# USB-IRIS-W1_MODULE.net
KiCad netlist of a schematic drawn in Altium Designer
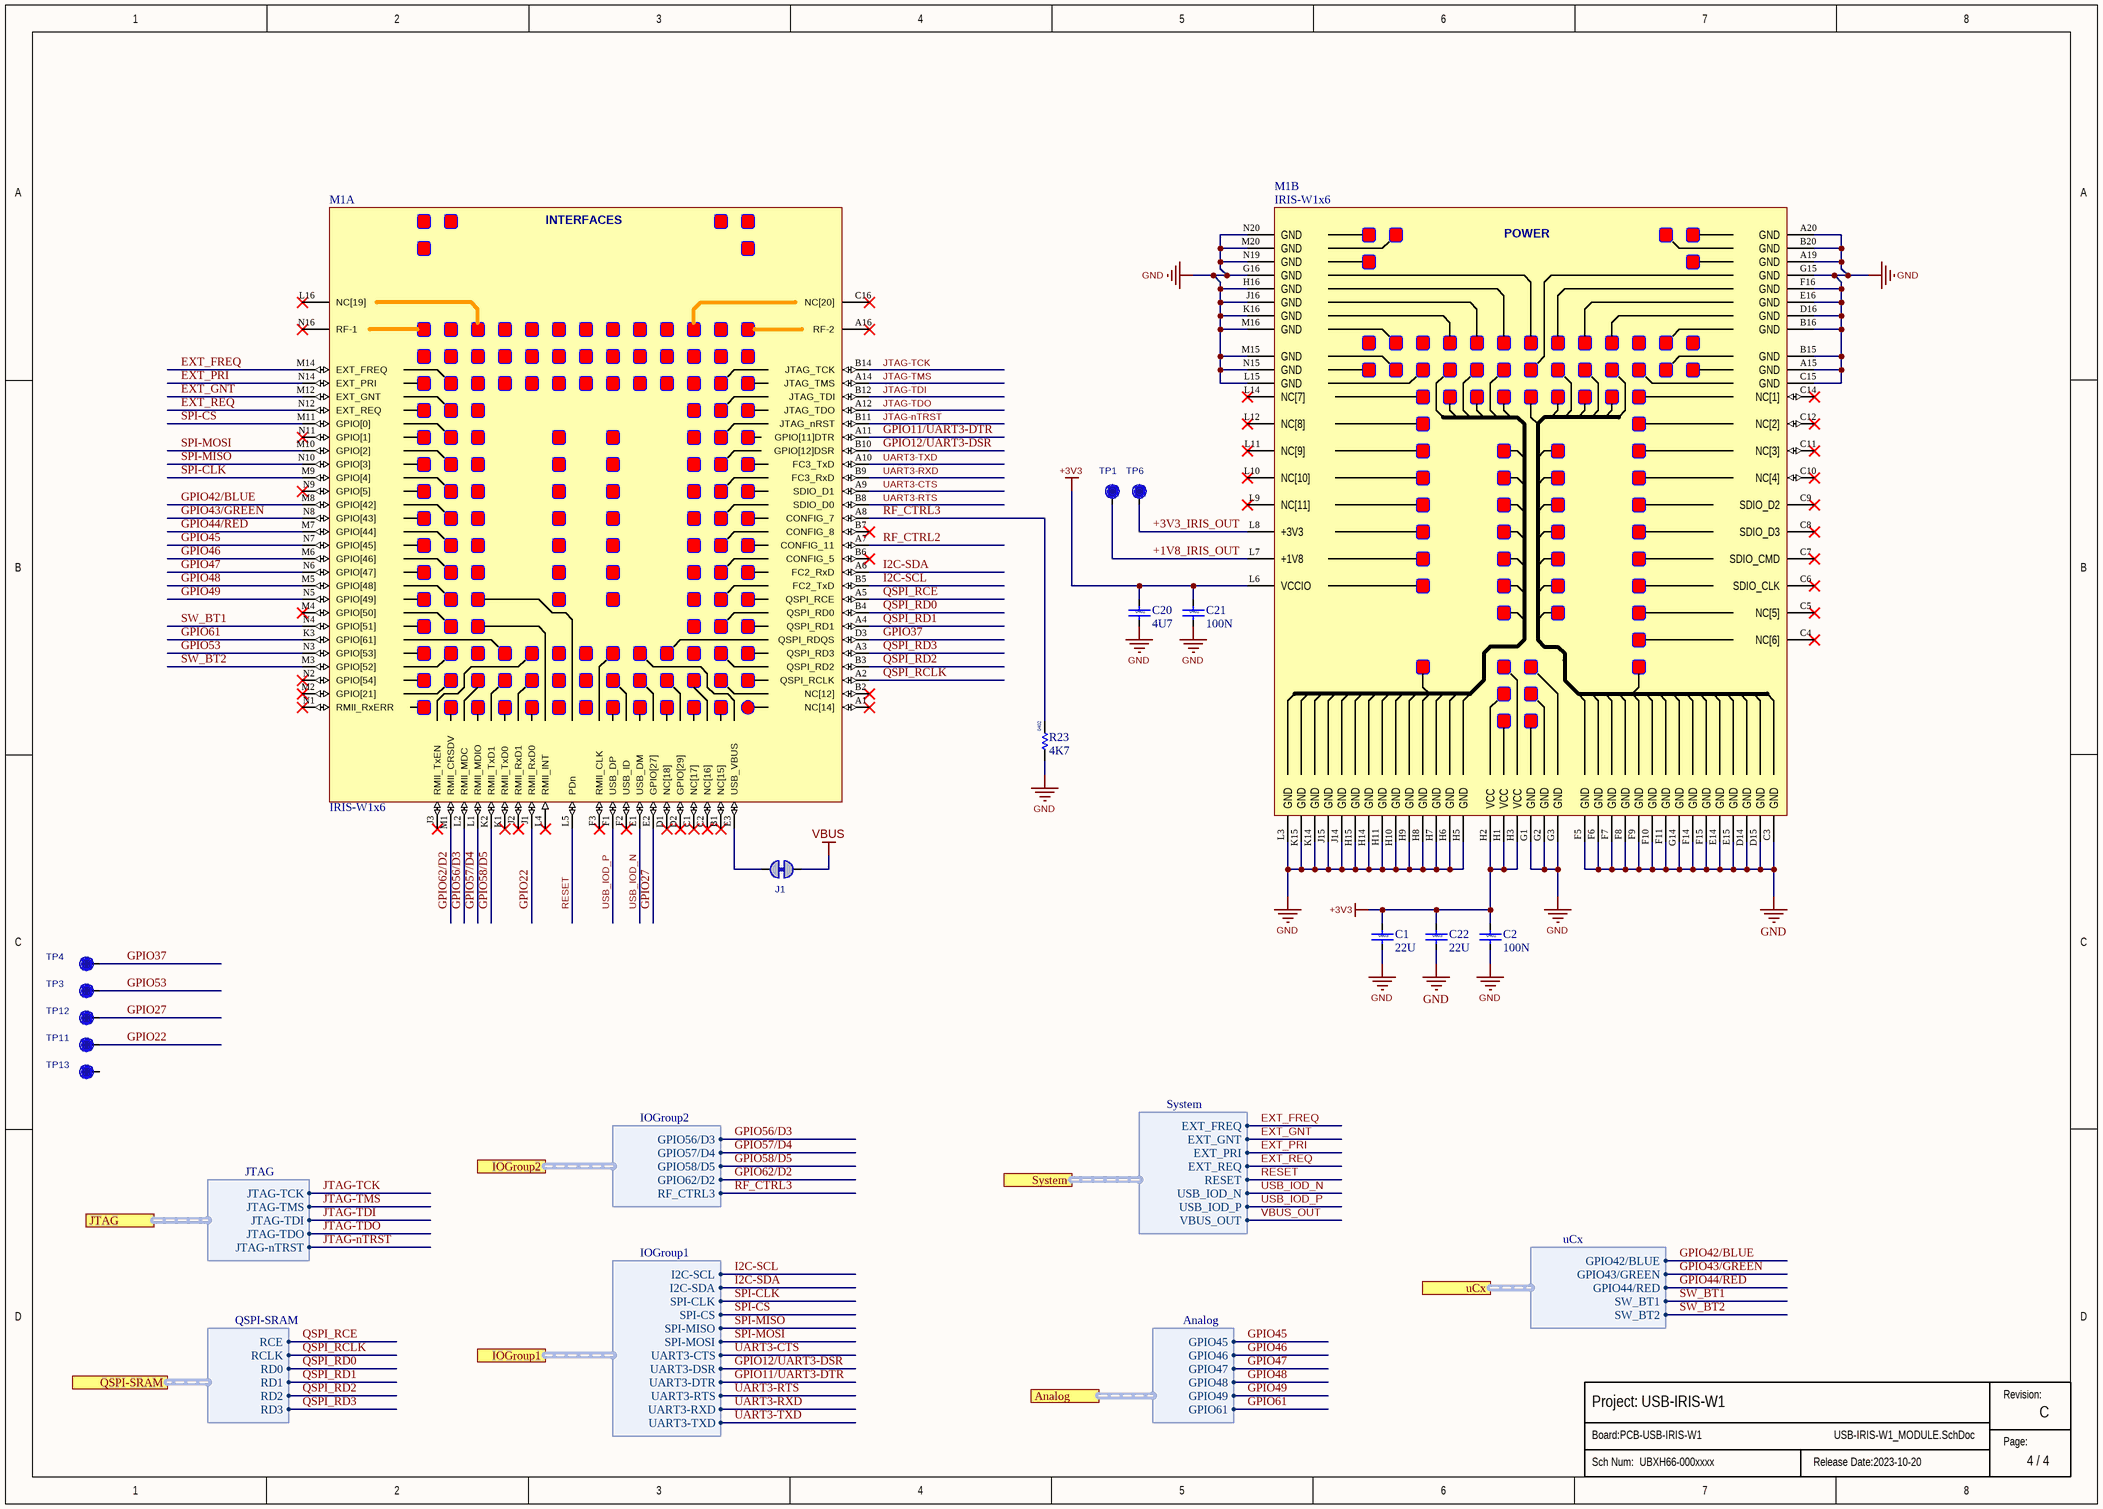
[diagram p0: USB-IRIS-W1_MODULE.SchDoc]

(export (version "E")
  (design (tool "Eeschema 10.0.6"))
  (components
    (comp (ref "C1")
      (value "22U")
      (footprint "Cap 0603")
      (description "CAP CER X5R 0603 22U 20% 10V")
      (fields
        (field (name "SIZE") "0603")
        (field (name "PART NUMBER") "UBXH01-0000150")
        (field (name "TOLERANCE") "20%")
        (field (name "EDITOR") "dario.antonaz")
        (field (name "RELEASED BY") "pasquale.scorca")
      )
      (libsource (lib "UBX_Parts_DB_Lib") (part "Cap Chip"))
    )
    (comp (ref "C2")
      (value "100N")
      (footprint "Cap 0402 HD")
      (description "CAP CER X5R 0402 100N 10% 10V")
      (fields
        (field (name "SIZE") "0402")
        (field (name "PART NUMBER") "UBXH01-2021002")
        (field (name "TOLERANCE") "10%")
        (field (name "EDITOR") "roland.rust")
        (field (name "RELEASED BY") "roland.rust")
      )
      (libsource (lib "UBX_Parts_DB_Lib") (part "Cap Chip"))
    )
    (comp (ref "C20")
      (value "4U7")
      (footprint "Cap_0402_1200Lx700Wx700H_600x600Pad_350G_FLX")
      (description "CAP CER X5R 0402 4U7 20% 10V")
      (fields
        (field (name "SIZE") "0402")
        (field (name "PART NUMBER") "UBXH01-0000243")
        (field (name "TOLERANCE") "20%")
        (field (name "EDITOR") "martin.pilik")
        (field (name "RELEASED BY") "fabrice.bret-dibat")
      )
      (libsource (lib "UBX_Parts_DB_Lib") (part "Cap Chip"))
    )
    (comp (ref "C21")
      (value "100N")
      (footprint "Cap 0402 HD")
      (description "CAP CER X5R 0402 100N 10% 10V")
      (fields
        (field (name "SIZE") "0402")
        (field (name "PART NUMBER") "UBXH01-2021002")
        (field (name "TOLERANCE") "10%")
        (field (name "EDITOR") "roland.rust")
        (field (name "RELEASED BY") "roland.rust")
      )
      (libsource (lib "UBX_Parts_DB_Lib") (part "Cap Chip"))
    )
    (comp (ref "C22")
      (value "22U")
      (footprint "Cap 0603")
      (description "CAP CER X5R 0603 22U 20% 10V")
      (fields
        (field (name "SIZE") "0603")
        (field (name "PART NUMBER") "UBXH01-0000150")
        (field (name "TOLERANCE") "20%")
        (field (name "EDITOR") "dario.antonaz")
        (field (name "RELEASED BY") "pasquale.scorca")
      )
      (libsource (lib "UBX_Parts_DB_Lib") (part "Cap Chip"))
    )
    (comp (ref "J1")
      (value "Solderbridge-ShortDNP")
      (footprint "Solderbridge-Short")
      (description "Solderbridge-Short")
      (fields (field (name "ADDED BY") "Paul B"))
      (libsource (lib "Schlib1") (part "Solderbridge-Short"))
    )
    (comp (ref "M1")
      (value "IRIS-W1x6")
      (footprint "IRIS-W1x6_LGA152")
      (description "SHORT RANGE STAND-ALONE MULTIRADIO MODULE U-BLOX IRIS-W106")
      (fields (field (name "PART NUMBER") "UBXH14-0000681") (field (name "EDITOR") "olof.viklund"))
      (libsource (lib "UBX_Parts_DB_Lib") (part "IRIS-W1_152pin"))
    )
    (comp (ref "R23")
      (value "4K7")
      (footprint "RES_0402_1100Lx600Wx400H_500x600Pad_400G_FLX")
      (description "RES THICK FILM CHIP 0402 4K7 5% 100mW")
      (fields
        (field (name "SIZE") "0402")
        (field (name "PART NUMBER") "UBXH18-0008065")
        (field (name "TOLERANCE") "5%")
        (field (name "EDITOR") "martin.frauchiger")
        (field (name "RELEASED BY") "martin.frauchiger")
      )
      (libsource (lib "UBX_Parts_DB_Lib") (part "Res sm"))
    )
    (comp (ref "TP1")
      (value "TP")
      (footprint "TP10R")
      (description "Testpoint, Round 1.0mm Dia")
      (fields
        (field (name "PART NUMBER") "TP10R")
        (field (name "ADDED BY") "Jeremy D")
        (field (name "CHECKED BY") "Paul B")
      )
      (libsource (lib "") (part "TP_R_1"))
    )
    (comp (ref "TP3")
      (value "TP")
      (footprint "TP10R")
      (description "Testpoint, Round 1.0mm Dia")
      (fields
        (field (name "PART NUMBER") "TP10R")
        (field (name "ADDED BY") "Jeremy D")
        (field (name "CHECKED BY") "Paul B")
      )
      (libsource (lib "LEGACY_Rigado_AltiumLib") (part "TP_R"))
    )
    (comp (ref "TP4")
      (value "TP")
      (footprint "TP10R")
      (description "Testpoint, Round 1.0mm Dia")
      (fields
        (field (name "PART NUMBER") "TP10R")
        (field (name "ADDED BY") "Jeremy D")
        (field (name "CHECKED BY") "Paul B")
      )
      (libsource (lib "LEGACY_Rigado_AltiumLib") (part "TP_R"))
    )
    (comp (ref "TP6")
      (value "TP")
      (footprint "TP10R")
      (description "Testpoint, Round 1.0mm Dia")
      (fields
        (field (name "PART NUMBER") "TP10R")
        (field (name "ADDED BY") "Jeremy D")
        (field (name "CHECKED BY") "Paul B")
      )
      (libsource (lib "") (part "TP_R_1"))
    )
    (comp (ref "TP11")
      (value "TP")
      (footprint "TP10R")
      (description "Testpoint, Round 1.0mm Dia")
      (fields
        (field (name "PART NUMBER") "TP10R")
        (field (name "ADDED BY") "Jeremy D")
        (field (name "CHECKED BY") "Paul B")
      )
      (libsource (lib "LEGACY_Rigado_AltiumLib") (part "TP_R"))
    )
    (comp (ref "TP12")
      (value "TP")
      (footprint "TP10R")
      (description "Testpoint, Round 1.0mm Dia")
      (fields
        (field (name "PART NUMBER") "TP10R")
        (field (name "ADDED BY") "Jeremy D")
        (field (name "CHECKED BY") "Paul B")
      )
      (libsource (lib "LEGACY_Rigado_AltiumLib") (part "TP_R"))
    )
    (comp (ref "TP13")
      (value "TP")
      (footprint "TP10R")
      (description "Testpoint, Round 1.0mm Dia")
      (fields
        (field (name "PART NUMBER") "TP10R")
        (field (name "ADDED BY") "Jeremy D")
        (field (name "CHECKED BY") "Paul B")
      )
      (libsource (lib "LEGACY_Rigado_AltiumLib") (part "TP_R"))
    )
  )
  (nets
    (net (code "8") (name "+3V3") (class "Default")
      (node (ref "C1") (pin "1") (pinfunction "1_1") (pintype "passive"))
      (node (ref "C2") (pin "1") (pinfunction "1_1") (pintype "passive"))
      (node (ref "C20") (pin "1") (pinfunction "1_1") (pintype "passive"))
      (node (ref "C21") (pin "1") (pinfunction "1_1") (pintype "passive"))
      (node (ref "C22") (pin "1") (pinfunction "1_1") (pintype "passive"))
      (node (ref "M1") (pin "H1") (pinfunction "VCC_H1") (pintype "power_in"))
      (node (ref "M1") (pin "H2") (pinfunction "VCC_H2") (pintype "power_in"))
      (node (ref "M1") (pin "H3") (pinfunction "VCC_H3") (pintype "power_in"))
      (node (ref "M1") (pin "L6") (pinfunction "VCCIO_L6") (pintype "power_in"))
    )
    (net (code "9") (name "/+1V8_IRIS_OUT") (class "Default")
      (node (ref "M1") (pin "L7") (pinfunction "+1V8_L7") (pintype "power_in"))
      (node (ref "TP1") (pin "1") (pintype "passive"))
    )
    (net (code "10") (name "/+3V3_IRIS_OUT") (class "Default")
      (node (ref "M1") (pin "L8") (pinfunction "+3V3_L8") (pintype "power_in"))
      (node (ref "TP6") (pin "1") (pintype "passive"))
    )
    (net (code "11") (name "/EXT_FREQ") (class "Default")
      (node (ref "M1") (pin "M14") (pinfunction "EXT_FREQ_M14") (pintype "bidirectional"))
    )
    (net (code "12") (name "/EXT_GNT") (class "Default")
      (node (ref "M1") (pin "M12") (pinfunction "EXT_GNT_M12") (pintype "bidirectional"))
    )
    (net (code "13") (name "/EXT_PRI") (class "Default")
      (node (ref "M1") (pin "N14") (pinfunction "EXT_PRI_N14") (pintype "bidirectional"))
    )
    (net (code "14") (name "/EXT_REQ") (class "Default")
      (node (ref "M1") (pin "N12") (pinfunction "EXT_REQ_N12") (pintype "bidirectional"))
    )
    (net (code "15") (name "/GPIO11{slash}UART3-DTR") (class "Default")
      (node (ref "M1") (pin "A11") (pinfunction "GPIO[11]DTR_A11") (pintype "bidirectional"))
    )
    (net (code "16") (name "/GPIO12{slash}UART3-DSR") (class "Default")
      (node (ref "M1") (pin "B10") (pinfunction "GPIO[12]DSR_B10") (pintype "bidirectional"))
    )
    (net (code "17") (name "/GPIO22") (class "Default")
      (node (ref "M1") (pin "J1") (pinfunction "RMII_RxD0_J1") (pintype "bidirectional"))
      (node (ref "TP11") (pin "1") (pintype "passive"))
    )
    (net (code "18") (name "/GPIO27") (class "Default")
      (node (ref "M1") (pin "E2") (pinfunction "GPIO[27]_E2") (pintype "bidirectional"))
      (node (ref "TP12") (pin "1") (pintype "passive"))
    )
    (net (code "19") (name "/GPIO37") (class "Default")
      (node (ref "M1") (pin "D3") (pinfunction "QSPI_RDQS_D3") (pintype "bidirectional"))
      (node (ref "TP4") (pin "1") (pintype "passive"))
    )
    (net (code "20") (name "/GPIO42{slash}BLUE") (class "Default")
      (node (ref "M1") (pin "M8") (pinfunction "GPIO[42]_M8") (pintype "bidirectional"))
    )
    (net (code "21") (name "/GPIO43{slash}GREEN") (class "Default")
      (node (ref "M1") (pin "N8") (pinfunction "GPIO[43]_N8") (pintype "bidirectional"))
    )
    (net (code "22") (name "/GPIO44{slash}RED") (class "Default")
      (node (ref "M1") (pin "M7") (pinfunction "GPIO[44]_M7") (pintype "bidirectional"))
    )
    (net (code "23") (name "/GPIO45") (class "Default")
      (node (ref "M1") (pin "N7") (pinfunction "GPIO[45]_N7") (pintype "bidirectional"))
    )
    (net (code "24") (name "/GPIO46") (class "Default")
      (node (ref "M1") (pin "M6") (pinfunction "GPIO[46]_M6") (pintype "bidirectional"))
    )
    (net (code "25") (name "/GPIO47") (class "Default")
      (node (ref "M1") (pin "N6") (pinfunction "GPIO[47]_N6") (pintype "bidirectional"))
    )
    (net (code "26") (name "/GPIO48") (class "Default")
      (node (ref "M1") (pin "M5") (pinfunction "GPIO[48]_M5") (pintype "bidirectional"))
    )
    (net (code "27") (name "/GPIO49") (class "Default")
      (node (ref "M1") (pin "N5") (pinfunction "GPIO[49]_N5") (pintype "bidirectional"))
    )
    (net (code "28") (name "/GPIO53") (class "Default")
      (node (ref "M1") (pin "N3") (pinfunction "GPIO[53]_N3") (pintype "bidirectional"))
      (node (ref "TP3") (pin "1") (pintype "passive"))
    )
    (net (code "29") (name "/GPIO56{slash}D3") (class "Default")
      (node (ref "M1") (pin "L2") (pinfunction "RMII_MDC_L2") (pintype "bidirectional"))
    )
    (net (code "30") (name "/GPIO57{slash}D4") (class "Default")
      (node (ref "M1") (pin "L1") (pinfunction "RMII_MDIO_L1") (pintype "bidirectional"))
    )
    (net (code "31") (name "/GPIO58{slash}D5") (class "Default")
      (node (ref "M1") (pin "K2") (pinfunction "RMII_TxD1_K2") (pintype "bidirectional"))
    )
    (net (code "32") (name "/GPIO61") (class "Default")
      (node (ref "M1") (pin "K3") (pinfunction "GPIO[61]_K3") (pintype "bidirectional"))
    )
    (net (code "33") (name "/GPIO62{slash}D2") (class "Default")
      (node (ref "M1") (pin "M1") (pinfunction "RMII_CRSDV_M1") (pintype "bidirectional"))
    )
    (net (code "34") (name "/I2C-SCL") (class "Default")
      (node (ref "M1") (pin "B5") (pinfunction "FC2_TxD_B5") (pintype "bidirectional"))
    )
    (net (code "35") (name "/I2C-SDA") (class "Default")
      (node (ref "M1") (pin "A6") (pinfunction "FC2_RxD_A6") (pintype "bidirectional"))
    )
    (net (code "36") (name "/JTAG-TCK") (class "Default")
      (node (ref "M1") (pin "B14") (pinfunction "JTAG_TCK_B14") (pintype "bidirectional"))
    )
    (net (code "37") (name "/JTAG-TDI") (class "Default")
      (node (ref "M1") (pin "B12") (pinfunction "JTAG_TDI_B12") (pintype "bidirectional"))
    )
    (net (code "38") (name "/JTAG-TDO") (class "Default")
      (node (ref "M1") (pin "A12") (pinfunction "JTAG_TDO_A12") (pintype "bidirectional"))
    )
    (net (code "39") (name "/JTAG-TMS") (class "Default")
      (node (ref "M1") (pin "A14") (pinfunction "JTAG_TMS_A14") (pintype "bidirectional"))
    )
    (net (code "40") (name "/JTAG-nTRST") (class "Default")
      (node (ref "M1") (pin "B11") (pinfunction "JTAG_nRST_B11") (pintype "bidirectional"))
    )
    (net (code "41") (name "/QSPI_RCE") (class "Default")
      (node (ref "M1") (pin "A5") (pinfunction "QSPI_RCE_A5") (pintype "bidirectional"))
    )
    (net (code "42") (name "/QSPI_RCLK") (class "Default")
      (node (ref "M1") (pin "A2") (pinfunction "QSPI_RCLK_A2") (pintype "bidirectional"))
    )
    (net (code "43") (name "/QSPI_RD0") (class "Default")
      (node (ref "M1") (pin "B4") (pinfunction "QSPI_RD0_B4") (pintype "bidirectional"))
    )
    (net (code "44") (name "/QSPI_RD1") (class "Default")
      (node (ref "M1") (pin "A4") (pinfunction "QSPI_RD1_A4") (pintype "bidirectional"))
    )
    (net (code "45") (name "/QSPI_RD2") (class "Default")
      (node (ref "M1") (pin "B3") (pinfunction "QSPI_RD2_B3") (pintype "bidirectional"))
    )
    (net (code "46") (name "/QSPI_RD3") (class "Default")
      (node (ref "M1") (pin "A3") (pinfunction "QSPI_RD3_A3") (pintype "bidirectional"))
    )
    (net (code "47") (name "/RESET") (class "Default")
      (node (ref "M1") (pin "L5") (pinfunction "PDn_L5") (pintype "bidirectional"))
    )
    (net (code "48") (name "/RF_CTRL2") (class "Default")
      (node (ref "M1") (pin "A7") (pinfunction "CONFIG_11_A7") (pintype "bidirectional"))
    )
    (net (code "49") (name "/RF_CTRL3") (class "Default")
      (node (ref "M1") (pin "A8") (pinfunction "CONFIG_7_A8") (pintype "bidirectional"))
      (node (ref "R23") (pin "2") (pinfunction "2_2") (pintype "passive"))
    )
    (net (code "50") (name "/SPI-CLK") (class "Default")
      (node (ref "M1") (pin "M9") (pinfunction "GPIO[4]_M9") (pintype "bidirectional"))
    )
    (net (code "51") (name "/SPI-CS") (class "Default")
      (node (ref "M1") (pin "M11") (pinfunction "GPIO[0]_M11") (pintype "bidirectional"))
    )
    (net (code "52") (name "/SPI-MISO") (class "Default")
      (node (ref "M1") (pin "N10") (pinfunction "GPIO[3]_N10") (pintype "bidirectional"))
    )
    (net (code "53") (name "/SPI-MOSI") (class "Default")
      (node (ref "M1") (pin "M10") (pinfunction "GPIO[2]_M10") (pintype "bidirectional"))
    )
    (net (code "54") (name "/SW_BT1") (class "Default")
      (node (ref "M1") (pin "N4") (pinfunction "GPIO[51]_N4") (pintype "bidirectional"))
    )
    (net (code "55") (name "/SW_BT2") (class "Default")
      (node (ref "M1") (pin "M3") (pinfunction "GPIO[52]_M3") (pintype "bidirectional"))
    )
    (net (code "56") (name "/UART3-CTS") (class "Default")
      (node (ref "M1") (pin "A9") (pinfunction "SDIO_D1_A9") (pintype "bidirectional"))
    )
    (net (code "57") (name "/UART3-RTS") (class "Default")
      (node (ref "M1") (pin "B8") (pinfunction "SDIO_D0_B8") (pintype "bidirectional"))
    )
    (net (code "58") (name "/UART3-RXD") (class "Default")
      (node (ref "M1") (pin "B9") (pinfunction "FC3_RxD_B9") (pintype "bidirectional"))
    )
    (net (code "59") (name "/UART3-TXD") (class "Default")
      (node (ref "M1") (pin "A10") (pinfunction "FC3_TxD_A10") (pintype "bidirectional"))
    )
    (net (code "60") (name "/USB_IOD_N") (class "Default")
      (node (ref "M1") (pin "E1") (pinfunction "USB_DM_E1") (pintype "bidirectional"))
    )
    (net (code "61") (name "/USB_IOD_P") (class "Default")
      (node (ref "M1") (pin "F1") (pinfunction "USB_DP_F1") (pintype "bidirectional"))
    )
    (net (code "70") (name "GND") (class "Default")
      (node (ref "C1") (pin "2") (pinfunction "2_2") (pintype "passive"))
      (node (ref "C2") (pin "2") (pinfunction "2_2") (pintype "passive"))
      (node (ref "C20") (pin "2") (pinfunction "2_2") (pintype "passive"))
      (node (ref "C21") (pin "2") (pinfunction "2_2") (pintype "passive"))
      (node (ref "C22") (pin "2") (pinfunction "2_2") (pintype "passive"))
      (node (ref "M1") (pin "A15") (pinfunction "GND_A15") (pintype "power_in"))
      (node (ref "M1") (pin "A19") (pinfunction "GND_A19") (pintype "passive"))
      (node (ref "M1") (pin "A20") (pinfunction "GND_A20") (pintype "passive"))
      (node (ref "M1") (pin "B15") (pinfunction "GND_B15") (pintype "power_in"))
      (node (ref "M1") (pin "B16") (pinfunction "GND_B16") (pintype "power_in"))
      (node (ref "M1") (pin "B20") (pinfunction "GND_B20") (pintype "passive"))
      (node (ref "M1") (pin "C15") (pinfunction "GND_C15") (pintype "power_in"))
      (node (ref "M1") (pin "C3") (pinfunction "GND_C3") (pintype "power_in"))
      (node (ref "M1") (pin "D14") (pinfunction "GND_D14") (pintype "power_in"))
      (node (ref "M1") (pin "D15") (pinfunction "GND_D15") (pintype "power_in"))
      (node (ref "M1") (pin "D16") (pinfunction "GND_D16") (pintype "power_in"))
      (node (ref "M1") (pin "E14") (pinfunction "GND_E14") (pintype "power_in"))
      (node (ref "M1") (pin "E15") (pinfunction "GND_E15") (pintype "power_in"))
      (node (ref "M1") (pin "E16") (pinfunction "GND_E16") (pintype "power_in"))
      (node (ref "M1") (pin "F10") (pinfunction "GND_F10") (pintype "power_in"))
      (node (ref "M1") (pin "F11") (pinfunction "GND_F11") (pintype "power_in"))
      (node (ref "M1") (pin "F14") (pinfunction "GND_F14") (pintype "power_in"))
      (node (ref "M1") (pin "F15") (pinfunction "GND_F15") (pintype "power_in"))
      (node (ref "M1") (pin "F16") (pinfunction "GND_F16") (pintype "power_in"))
      (node (ref "M1") (pin "F5") (pinfunction "GND_F5") (pintype "power_in"))
      (node (ref "M1") (pin "F6") (pinfunction "GND_F6") (pintype "power_in"))
      (node (ref "M1") (pin "F7") (pinfunction "GND_F7") (pintype "power_in"))
      (node (ref "M1") (pin "F8") (pinfunction "GND_F8") (pintype "power_in"))
      (node (ref "M1") (pin "F9") (pinfunction "GND_F9") (pintype "power_in"))
      (node (ref "M1") (pin "G1") (pinfunction "GND_G1") (pintype "power_in"))
      (node (ref "M1") (pin "G14") (pinfunction "GND_G14") (pintype "power_in"))
      (node (ref "M1") (pin "G15") (pinfunction "GND_G15") (pintype "power_in"))
      (node (ref "M1") (pin "G16") (pinfunction "GND_G16") (pintype "power_in"))
      (node (ref "M1") (pin "G2") (pinfunction "GND_G2") (pintype "power_in"))
      (node (ref "M1") (pin "G3") (pinfunction "GND_G3") (pintype "power_in"))
      (node (ref "M1") (pin "H10") (pinfunction "GND_H10") (pintype "power_in"))
      (node (ref "M1") (pin "H11") (pinfunction "GND_H11") (pintype "power_in"))
      (node (ref "M1") (pin "H14") (pinfunction "GND_H14") (pintype "power_in"))
      (node (ref "M1") (pin "H15") (pinfunction "GND_H15") (pintype "power_in"))
      (node (ref "M1") (pin "H16") (pinfunction "GND_H16") (pintype "power_in"))
      (node (ref "M1") (pin "H5") (pinfunction "GND_H5") (pintype "power_in"))
      (node (ref "M1") (pin "H6") (pinfunction "GND_H6") (pintype "power_in"))
      (node (ref "M1") (pin "H7") (pinfunction "GND_H7") (pintype "power_in"))
      (node (ref "M1") (pin "H8") (pinfunction "GND_H8") (pintype "power_in"))
      (node (ref "M1") (pin "H9") (pinfunction "GND_H9") (pintype "power_in"))
      (node (ref "M1") (pin "J14") (pinfunction "GND_J14") (pintype "power_in"))
      (node (ref "M1") (pin "J15") (pinfunction "GND_J15") (pintype "power_in"))
      (node (ref "M1") (pin "J16") (pinfunction "GND_J16") (pintype "power_in"))
      (node (ref "M1") (pin "K14") (pinfunction "GND_K14") (pintype "power_in"))
      (node (ref "M1") (pin "K15") (pinfunction "GND_K15") (pintype "power_in"))
      (node (ref "M1") (pin "K16") (pinfunction "GND_K16") (pintype "power_in"))
      (node (ref "M1") (pin "L15") (pinfunction "GND_L15") (pintype "power_in"))
      (node (ref "M1") (pin "L3") (pinfunction "GND_L3") (pintype "power_in"))
      (node (ref "M1") (pin "M15") (pinfunction "GND_M15") (pintype "power_in"))
      (node (ref "M1") (pin "M16") (pinfunction "GND_M16") (pintype "power_in"))
      (node (ref "M1") (pin "M20") (pinfunction "GND_M20") (pintype "passive"))
      (node (ref "M1") (pin "N15") (pinfunction "GND_N15") (pintype "power_in"))
      (node (ref "M1") (pin "N19") (pinfunction "GND_N19") (pintype "passive"))
      (node (ref "M1") (pin "N20") (pinfunction "GND_N20") (pintype "passive"))
      (node (ref "R23") (pin "1") (pinfunction "1_1") (pintype "passive"))
    )
    (net (code "71") (name "Net-(M1A-USB_VBUS)") (class "Default")
      (node (ref "J1") (pin "2") (pinfunction "2_2") (pintype "passive"))
      (node (ref "M1") (pin "E3") (pinfunction "USB_VBUS_E3") (pintype "bidirectional"))
    )
    (net (code "72") (name "VBUS") (class "Default")
      (node (ref "J1") (pin "1") (pinfunction "1_1") (pintype "passive"))
    )
    (net (code "73") (name "unconnected-(M1A-CONFIG_5-PadB6)") (class "Default")
      (node (ref "M1") (pin "B6") (pinfunction "CONFIG_5_B6") (pintype "bidirectional+no_connect"))
    )
    (net (code "74") (name "unconnected-(M1A-CONFIG_8-PadB7)") (class "Default")
      (node (ref "M1") (pin "B7") (pinfunction "CONFIG_8_B7") (pintype "bidirectional+no_connect"))
    )
    (net (code "75") (name "unconnected-(M1A-GPIO[1]-PadN11)") (class "Default")
      (node (ref "M1") (pin "N11") (pinfunction "GPIO[1]_N11") (pintype "bidirectional+no_connect"))
    )
    (net (code "76") (name "unconnected-(M1A-GPIO[5]-PadN9)") (class "Default")
      (node (ref "M1") (pin "N9") (pinfunction "GPIO[5]_N9") (pintype "bidirectional+no_connect"))
    )
    (net (code "77") (name "unconnected-(M1A-GPIO[21]-PadM2)") (class "Default")
      (node (ref "M1") (pin "M2") (pinfunction "GPIO[21]_M2") (pintype "bidirectional+no_connect"))
    )
    (net (code "78") (name "unconnected-(M1A-GPIO[29]-PadD2)") (class "Default")
      (node (ref "M1") (pin "D2") (pinfunction "GPIO[29]_D2") (pintype "bidirectional+no_connect"))
    )
    (net (code "79") (name "unconnected-(M1A-GPIO[50]-PadM4)") (class "Default")
      (node (ref "M1") (pin "M4") (pinfunction "GPIO[50]_M4") (pintype "bidirectional+no_connect"))
    )
    (net (code "80") (name "unconnected-(M1A-GPIO[54]-PadN2)") (class "Default")
      (node (ref "M1") (pin "N2") (pinfunction "GPIO[54]_N2") (pintype "bidirectional+no_connect"))
    )
    (net (code "81") (name "unconnected-(M1A-NC[12]-PadB2)") (class "Default")
      (node (ref "M1") (pin "B2") (pinfunction "NC[12]_B2") (pintype "bidirectional+no_connect"))
    )
    (net (code "82") (name "unconnected-(M1A-NC[14]-PadA1)") (class "Default")
      (node (ref "M1") (pin "A1") (pinfunction "NC[14]_A1") (pintype "bidirectional+no_connect"))
    )
    (net (code "83") (name "unconnected-(M1A-NC[15]-PadB1)") (class "Default")
      (node (ref "M1") (pin "B1") (pinfunction "NC[15]_B1") (pintype "bidirectional+no_connect"))
    )
    (net (code "84") (name "unconnected-(M1A-NC[16]-PadC2)") (class "Default")
      (node (ref "M1") (pin "C2") (pinfunction "NC[16]_C2") (pintype "bidirectional+no_connect"))
    )
    (net (code "85") (name "unconnected-(M1A-NC[17]-PadC1)") (class "Default")
      (node (ref "M1") (pin "C1") (pinfunction "NC[17]_C1") (pintype "bidirectional+no_connect"))
    )
    (net (code "86") (name "unconnected-(M1A-NC[18]-PadD1)") (class "Default")
      (node (ref "M1") (pin "D1") (pinfunction "NC[18]_D1") (pintype "bidirectional+no_connect"))
    )
    (net (code "87") (name "unconnected-(M1A-NC[19]-PadL16)") (class "Default")
      (node (ref "M1") (pin "L16") (pinfunction "NC[19]_L16") (pintype "passive+no_connect"))
    )
    (net (code "88") (name "unconnected-(M1A-NC[20]-PadC16)") (class "Default")
      (node (ref "M1") (pin "C16") (pinfunction "NC[20]_C16") (pintype "passive+no_connect"))
    )
    (net (code "89") (name "unconnected-(M1A-RF-1-PadN16)") (class "Default")
      (node (ref "M1") (pin "N16") (pinfunction "RF-1_N16") (pintype "passive+no_connect"))
    )
    (net (code "90") (name "unconnected-(M1A-RF-2-PadA16)") (class "Default")
      (node (ref "M1") (pin "A16") (pinfunction "RF-2_A16") (pintype "passive+no_connect"))
    )
    (net (code "91") (name "unconnected-(M1A-RMII_CLK-PadF3)") (class "Default")
      (node (ref "M1") (pin "F3") (pinfunction "RMII_CLK_F3") (pintype "bidirectional+no_connect"))
    )
    (net (code "92") (name "unconnected-(M1A-RMII_INT-PadL4)") (class "Default")
      (node (ref "M1") (pin "L4") (pinfunction "RMII_INT_L4") (pintype "input+no_connect"))
    )
    (net (code "93") (name "unconnected-(M1A-RMII_RxD1-PadJ2)") (class "Default")
      (node (ref "M1") (pin "J2") (pinfunction "RMII_RxD1_J2") (pintype "bidirectional+no_connect"))
    )
    (net (code "94") (name "unconnected-(M1A-RMII_RxERR-PadN1)") (class "Default")
      (node (ref "M1") (pin "N1") (pinfunction "RMII_RxERR_N1") (pintype "bidirectional+no_connect"))
    )
    (net (code "95") (name "unconnected-(M1A-RMII_TxD0-PadK1)") (class "Default")
      (node (ref "M1") (pin "K1") (pinfunction "RMII_TxD0_K1") (pintype "bidirectional+no_connect"))
    )
    (net (code "96") (name "unconnected-(M1A-RMII_TxEN-PadJ3)") (class "Default")
      (node (ref "M1") (pin "J3") (pinfunction "RMII_TxEN_J3") (pintype "bidirectional+no_connect"))
    )
    (net (code "97") (name "unconnected-(M1A-USB_ID-PadF2)") (class "Default")
      (node (ref "M1") (pin "F2") (pinfunction "USB_ID_F2") (pintype "bidirectional+no_connect"))
    )
    (net (code "98") (name "unconnected-(M1B-NC[1]-PadC14)") (class "Default")
      (node (ref "M1") (pin "C14") (pinfunction "NC[1]_C14") (pintype "bidirectional+no_connect"))
    )
    (net (code "99") (name "unconnected-(M1B-NC[2]-PadC12)") (class "Default")
      (node (ref "M1") (pin "C12") (pinfunction "NC[2]_C12") (pintype "bidirectional+no_connect"))
    )
    (net (code "100") (name "unconnected-(M1B-NC[3]-PadC11)") (class "Default")
      (node (ref "M1") (pin "C11") (pinfunction "NC[3]_C11") (pintype "bidirectional+no_connect"))
    )
    (net (code "101") (name "unconnected-(M1B-NC[4]-PadC10)") (class "Default")
      (node (ref "M1") (pin "C10") (pinfunction "NC[4]_C10") (pintype "bidirectional+no_connect"))
    )
    (net (code "102") (name "unconnected-(M1B-NC[5]-PadC5)") (class "Default")
      (node (ref "M1") (pin "C5") (pinfunction "NC[5]_C5") (pintype "passive+no_connect"))
    )
    (net (code "103") (name "unconnected-(M1B-NC[6]-PadC4)") (class "Default")
      (node (ref "M1") (pin "C4") (pinfunction "NC[6]_C4") (pintype "passive+no_connect"))
    )
    (net (code "104") (name "unconnected-(M1B-NC[7]-PadL14)") (class "Default")
      (node (ref "M1") (pin "L14") (pinfunction "NC[7]_L14") (pintype "passive+no_connect"))
    )
    (net (code "105") (name "unconnected-(M1B-NC[8]-PadL12)") (class "Default")
      (node (ref "M1") (pin "L12") (pinfunction "NC[8]_L12") (pintype "passive+no_connect"))
    )
    (net (code "106") (name "unconnected-(M1B-NC[9]-PadL11)") (class "Default")
      (node (ref "M1") (pin "L11") (pinfunction "NC[9]_L11") (pintype "passive+no_connect"))
    )
    (net (code "107") (name "unconnected-(M1B-NC[10]-PadL10)") (class "Default")
      (node (ref "M1") (pin "L10") (pinfunction "NC[10]_L10") (pintype "passive+no_connect"))
    )
    (net (code "108") (name "unconnected-(M1B-NC[11]-PadL9)") (class "Default")
      (node (ref "M1") (pin "L9") (pinfunction "NC[11]_L9") (pintype "passive+no_connect"))
    )
    (net (code "109") (name "unconnected-(M1B-SDIO_CLK-PadC6)") (class "Default")
      (node (ref "M1") (pin "C6") (pinfunction "SDIO_CLK_C6") (pintype "passive+no_connect"))
    )
    (net (code "110") (name "unconnected-(M1B-SDIO_CMD-PadC7)") (class "Default")
      (node (ref "M1") (pin "C7") (pinfunction "SDIO_CMD_C7") (pintype "passive+no_connect"))
    )
    (net (code "111") (name "unconnected-(M1B-SDIO_D2-PadC9)") (class "Default")
      (node (ref "M1") (pin "C9") (pinfunction "SDIO_D2_C9") (pintype "passive+no_connect"))
    )
    (net (code "112") (name "unconnected-(M1B-SDIO_D3-PadC8)") (class "Default")
      (node (ref "M1") (pin "C8") (pinfunction "SDIO_D3_C8") (pintype "passive+no_connect"))
    )
    (net (code "113") (name "unconnected-(TP13-Pad1)") (class "Default")
      (node (ref "TP13") (pin "1") (pintype "passive"))
    )
  )
)
